# Thermostat_Master.net
KiCad netlist of a schematic drawn in Altium Designer
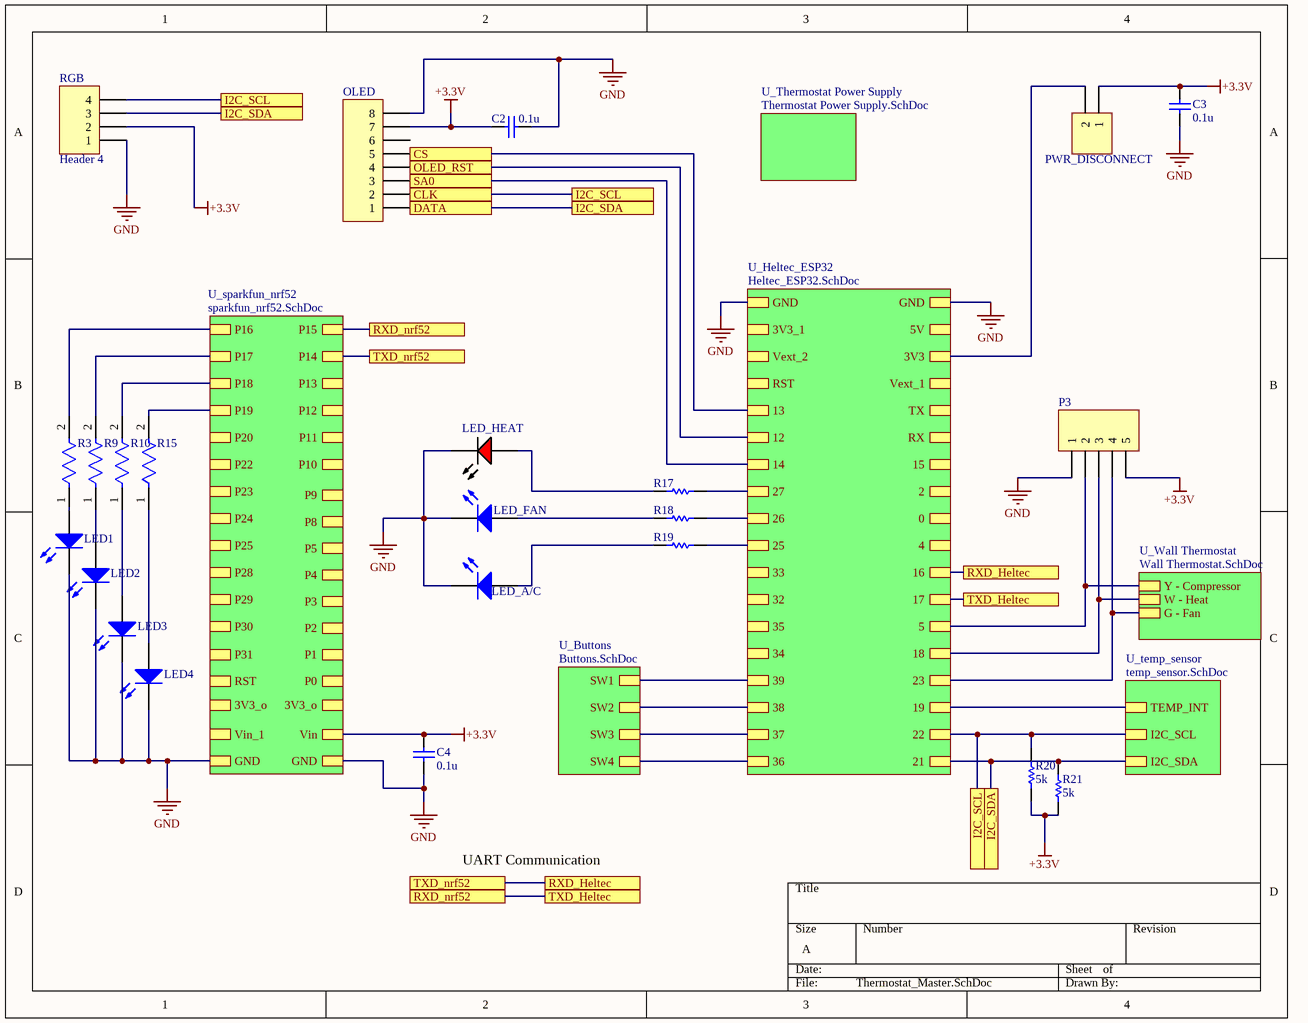
[diagram p0: Thermostat_Master.SchDoc]

(export (version "E")
  (design (tool "Eeschema 10.0.6"))
  (components
    (comp (ref "C2")
      (value "0.1u")
      (footprint "CAPC2013X145X50LL20T25")
      (description "C0805C104Z5VACTU")
      (fields (field (name "MANUFACTURER") "Kemet"))
      (libsource (lib "Altium Content Vault") (part "CAP"))
    )
    (comp (ref "C3")
      (value "0.1u")
      (footprint "CAPC2013X145X50LL20T25")
      (description "C0805C104Z5VACTU")
      (fields (field (name "MANUFACTURER") "Kemet"))
      (libsource (lib "Altium Content Vault") (part "CAP"))
    )
    (comp (ref "C4")
      (value "0.1u")
      (footprint "CAPC2013X145X50LL20T25")
      (description "C0805C104Z5VACTU")
      (fields (field (name "MANUFACTURER") "Kemet"))
      (libsource (lib "Altium Content Vault") (part "CAP"))
    )
    (comp (ref "LED1")
      (value "~")
      (footprint "1206_A")
      (description "QTLP650C4TR\r\n1206 green led")
      (fields (field (name "PARTNUMBER") "150120VS75000") (field (name "MANUFACTURER") "Wuerth Elektronik"))
      (libsource (lib "Altium Content Vault") (part "WE-LED_K1A2-2"))
    )
    (comp (ref "LED2")
      (value "~")
      (footprint "1206_A")
      (description "QTLP650C4TR\r\n1206 green led")
      (fields (field (name "PARTNUMBER") "150120VS75000") (field (name "MANUFACTURER") "Wuerth Elektronik"))
      (libsource (lib "Altium Content Vault") (part "WE-LED_K1A2-2"))
    )
    (comp (ref "LED3")
      (value "~")
      (footprint "1206_A")
      (description "QTLP650C4TR\r\n1206 green led")
      (fields (field (name "PARTNUMBER") "150120VS75000") (field (name "MANUFACTURER") "Wuerth Elektronik"))
      (libsource (lib "Altium Content Vault") (part "WE-LED_K1A2-2"))
    )
    (comp (ref "LED4")
      (value "~")
      (footprint "1206_A")
      (description "QTLP650C4TR\r\n1206 green led")
      (fields (field (name "PARTNUMBER") "150120VS75000") (field (name "MANUFACTURER") "Wuerth Elektronik"))
      (libsource (lib "Altium Content Vault") (part "WE-LED_K1A2-2"))
    )
    (comp (ref "LED_A/C")
      (value "~")
      (footprint "1206_A")
      (description "QTLP650C4TR\r\n1206 green led")
      (fields (field (name "PARTNUMBER") "LTST-C150TBKT"))
      (libsource (lib "Altium Content Vault") (part "WE-LED_K1A2-2"))
    )
    (comp (ref "LED_FAN")
      (value "~")
      (footprint "1206_A")
      (description "LTST-C150GKT\r\n1206 green led")
      (fields (field (name "PARTNUMBER") "LTST-C150GKT"))
      (libsource (lib "Altium Content Vault") (part "WE-LED_K1A2-2"))
    )
    (comp (ref "LED_HEAT")
      (value "LTST-C150KRKT")
      (footprint "LTST-C150KRKT_V")
      (description "LED Red, 62.5 mW, 50 mA, -30 to 85 degC, 2-Pin SMD, RoHS, Tape and Reel")
      (fields (field (name "MANUFACTURER") "Lite-On"))
      (libsource (lib "Altium Content Vault") (part "LED-RED-AK-2"))
    )
    (comp (ref "OLED")
      (value "Header 8")
      (footprint "HDR1X8")
      (description "Header, 8-Pin")
      (fields (field (name "PUBLISHER") "Altium Limited"))
      (libsource (lib "Miscellaneous Connectors") (part "Header 8"))
    )
    (comp (ref "P3")
      (value "Header 5")
      (footprint "HDR1X5")
      (description "Header, 5-Pin")
      (fields (field (name "PUBLISHER") "Altium Limited"))
      (libsource (lib "Miscellaneous Connectors") (part "Header 5"))
    )
    (comp (ref "PWR_DISCONNECT")
      (value "Header 2")
      (footprint "HDR1X2")
      (description "Header, 2-Pin")
      (fields (field (name "PUBLISHER") "Altium Limited"))
      (libsource (lib "Miscellaneous Connectors") (part "Header 2"))
    )
    (comp (ref "R3")
      (value "~")
      (footprint "FP-RC1206-MFG")
      (description "360 ohms resistor \r\n1206 package")
      (fields
        (field (name "MANUFACTURER PART NUMBER") "RC1206JR-070RL")
        (field (name "MANUFACTURER") "YAGEO")
      )
      (libsource (lib "Altium Content Vault") (part "1029c3af85768c4190bb7ad29bc67b5"))
    )
    (comp (ref "R9")
      (value "~")
      (footprint "FP-RC1206-MFG")
      (description "360 ohms resistor \r\n1206 package")
      (fields
        (field (name "MANUFACTURER PART NUMBER") "RC1206JR-070RL")
        (field (name "MANUFACTURER") "YAGEO")
      )
      (libsource (lib "Altium Content Vault") (part "1029c3af85768c4190bb7ad29bc67b5"))
    )
    (comp (ref "R10")
      (value "~")
      (footprint "FP-RC1206-MFG")
      (description "360 ohms resistor \r\n1206 package")
      (fields
        (field (name "MANUFACTURER PART NUMBER") "RC1206JR-070RL")
        (field (name "MANUFACTURER") "YAGEO")
      )
      (libsource (lib "Altium Content Vault") (part "1029c3af85768c4190bb7ad29bc67b5"))
    )
    (comp (ref "R15")
      (value "~")
      (footprint "FP-RC1206-MFG")
      (description "360 ohms resistor \r\n1206 package")
      (fields
        (field (name "MANUFACTURER PART NUMBER") "RC1206JR-070RL")
        (field (name "MANUFACTURER") "YAGEO")
      )
      (libsource (lib "Altium Content Vault") (part "1029c3af85768c4190bb7ad29bc67b5"))
    )
    (comp (ref "R17")
      (value "RC0805FR-07100RL")
      (footprint "RESC2013X60X35ML10T20")
      (description "Chip Resistor, 100 Ohm, +/-1%, 0.125 W, -55 to 155 degC, 0805 (2012 Metric), RoHS, Tape and Reel")
      (fields (field (name "TOLERANCE") "1%") (field (name "MANUFACTURER") "Yageo"))
      (libsource (lib "Altium Content Vault") (part "RES-2"))
    )
    (comp (ref "R18")
      (value "RC0805FR-07100RL")
      (footprint "RESC2013X60X35ML10T20")
      (description "Chip Resistor, 100 Ohm, +/-1%, 0.125 W, -55 to 155 degC, 0805 (2012 Metric), RoHS, Tape and Reel")
      (fields (field (name "TOLERANCE") "1%") (field (name "MANUFACTURER") "Yageo"))
      (libsource (lib "Altium Content Vault") (part "RES-2"))
    )
    (comp (ref "R19")
      (value "RC0805FR-07100RL")
      (footprint "RESC2013X60X35ML10T20")
      (description "Chip Resistor, 100 Ohm, +/-1%, 0.125 W, -55 to 155 degC, 0805 (2012 Metric), RoHS, Tape and Reel")
      (fields (field (name "TOLERANCE") "1%") (field (name "MANUFACTURER") "Yageo"))
      (libsource (lib "Altium Content Vault") (part "RES-2"))
    )
    (comp (ref "R20")
      (value "5k")
      (footprint "RESC2013X70X40LL20T20")
      (description "2012")
      (fields (field (name "PART NUMBER") "ERJ-6GEYJ471V") (field (name "MANUFACTURER") "Panasonic"))
      (libsource (lib "Altium Content Vault") (part "RES"))
    )
    (comp (ref "R21")
      (value "5k")
      (footprint "RESC2013X70X40LL20T20")
      (description "2012")
      (fields (field (name "PART NUMBER") "ERJ-6GEYJ471V") (field (name "MANUFACTURER") "Panasonic"))
      (libsource (lib "Altium Content Vault") (part "RES"))
    )
    (comp (ref "RGB")
      (value "Header 4")
      (footprint "HDR1X4")
      (description "Header, 4-Pin")
      (fields (field (name "PUBLISHER") "Altium Limited"))
      (libsource (lib "Miscellaneous Connectors") (part "Header 4"))
    )
  )
  (nets
    (net (code "1") (name "+3.3V") (class "Default")
      (node (ref "C2") (pin "2") (pinfunction "2_2") (pintype "passive"))
      (node (ref "C3") (pin "2") (pinfunction "2_2") (pintype "passive"))
      (node (ref "C4") (pin "2") (pinfunction "2_2") (pintype "passive"))
      (node (ref "OLED") (pin "7") (pinfunction "7_7") (pintype "passive"))
      (node (ref "P3") (pin "5") (pinfunction "5_5") (pintype "passive"))
      (node (ref "PWR_DISCONNECT") (pin "1") (pinfunction "1_1") (pintype "passive"))
      (node (ref "R20") (pin "1") (pinfunction "1_1") (pintype "passive"))
      (node (ref "R21") (pin "1") (pinfunction "1_1") (pintype "passive"))
      (node (ref "RGB") (pin "2") (pinfunction "2_2") (pintype "passive"))
    )
    (net (code "4") (name "/3V3") (class "Default")
      (node (ref "PWR_DISCONNECT") (pin "2") (pinfunction "2_2") (pintype "passive"))
    )
    (net (code "9") (name "/5") (class "Default")
      (node (ref "P3") (pin "2") (pinfunction "2_2") (pintype "passive"))
    )
    (net (code "12") (name "/18") (class "Default")
      (node (ref "P3") (pin "3") (pinfunction "3_3") (pintype "passive"))
    )
    (net (code "14") (name "/23") (class "Default")
      (node (ref "P3") (pin "4") (pinfunction "4_4") (pintype "passive"))
    )
    (net (code "15") (name "/25") (class "Default")
      (node (ref "R19") (pin "2") (pinfunction "2_2") (pintype "passive"))
    )
    (net (code "16") (name "/26") (class "Default")
      (node (ref "R18") (pin "2") (pinfunction "2_2") (pintype "passive"))
    )
    (net (code "17") (name "/27") (class "Default")
      (node (ref "R17") (pin "2") (pinfunction "2_2") (pintype "passive"))
    )
    (net (code "26") (name "/CLK") (class "Default")
      (node (ref "OLED") (pin "2") (pinfunction "2_2") (pintype "passive"))
      (node (ref "R20") (pin "2") (pinfunction "2_2") (pintype "passive"))
      (node (ref "RGB") (pin "4") (pinfunction "4_4") (pintype "passive"))
    )
    (net (code "27") (name "/CS") (class "Default")
      (node (ref "OLED") (pin "5") (pinfunction "5_5") (pintype "passive"))
    )
    (net (code "28") (name "/DATA") (class "Default")
      (node (ref "OLED") (pin "1") (pinfunction "1_1") (pintype "passive"))
      (node (ref "R21") (pin "2") (pinfunction "2_2") (pintype "passive"))
      (node (ref "RGB") (pin "3") (pinfunction "3_3") (pintype "passive"))
    )
    (net (code "29") (name "/OLED_RST") (class "Default")
      (node (ref "OLED") (pin "4") (pinfunction "4_4") (pintype "passive"))
    )
    (net (code "42") (name "/P16") (class "Default")
      (node (ref "R3") (pin "2") (pinfunction "2_2") (pintype "passive"))
    )
    (net (code "43") (name "/P17") (class "Default")
      (node (ref "R9") (pin "2") (pinfunction "2_2") (pintype "passive"))
    )
    (net (code "44") (name "/P18") (class "Default")
      (node (ref "R10") (pin "2") (pinfunction "2_2") (pintype "passive"))
    )
    (net (code "45") (name "/P19") (class "Default")
      (node (ref "R15") (pin "2") (pinfunction "2_2") (pintype "passive"))
    )
    (net (code "60") (name "/SA0") (class "Default")
      (node (ref "OLED") (pin "3") (pinfunction "3_3") (pintype "passive"))
    )
    (net (code "65") (name "GND") (class "Default")
      (node (ref "C2") (pin "1") (pinfunction "1_1") (pintype "passive"))
      (node (ref "C3") (pin "1") (pinfunction "1_1") (pintype "passive"))
      (node (ref "C4") (pin "1") (pinfunction "1_1") (pintype "passive"))
      (node (ref "LED1") (pin "1") (pinfunction "K_1") (pintype "passive"))
      (node (ref "LED2") (pin "1") (pinfunction "K_1") (pintype "passive"))
      (node (ref "LED3") (pin "1") (pinfunction "K_1") (pintype "passive"))
      (node (ref "LED4") (pin "1") (pinfunction "K_1") (pintype "passive"))
      (node (ref "LED_A/C") (pin "1") (pinfunction "K_1") (pintype "passive"))
      (node (ref "LED_FAN") (pin "1") (pinfunction "K_1") (pintype "passive"))
      (node (ref "LED_HEAT") (pin "2") (pinfunction "K_2") (pintype "passive"))
      (node (ref "OLED") (pin "8") (pinfunction "8_8") (pintype "passive"))
      (node (ref "P3") (pin "1") (pinfunction "1_1") (pintype "passive"))
      (node (ref "RGB") (pin "1") (pinfunction "1_1") (pintype "passive"))
    )
    (net (code "66") (name "Net-(LED1-A)") (class "Default")
      (node (ref "LED1") (pin "2") (pinfunction "A_2") (pintype "passive"))
      (node (ref "R3") (pin "1") (pinfunction "1_1") (pintype "passive"))
    )
    (net (code "67") (name "Net-(LED2-A)") (class "Default")
      (node (ref "LED2") (pin "2") (pinfunction "A_2") (pintype "passive"))
      (node (ref "R9") (pin "1") (pinfunction "1_1") (pintype "passive"))
    )
    (net (code "68") (name "Net-(LED3-A)") (class "Default")
      (node (ref "LED3") (pin "2") (pinfunction "A_2") (pintype "passive"))
      (node (ref "R10") (pin "1") (pinfunction "1_1") (pintype "passive"))
    )
    (net (code "69") (name "Net-(LED4-A)") (class "Default")
      (node (ref "LED4") (pin "2") (pinfunction "A_2") (pintype "passive"))
      (node (ref "R15") (pin "1") (pinfunction "1_1") (pintype "passive"))
    )
    (net (code "70") (name "Net-(LED_A/C-A)") (class "Default")
      (node (ref "LED_A/C") (pin "2") (pinfunction "A_2") (pintype "passive"))
      (node (ref "R19") (pin "1") (pinfunction "1_1") (pintype "passive"))
    )
    (net (code "71") (name "Net-(LED_FAN-A)") (class "Default")
      (node (ref "LED_FAN") (pin "2") (pinfunction "A_2") (pintype "passive"))
      (node (ref "R18") (pin "1") (pinfunction "1_1") (pintype "passive"))
    )
    (net (code "72") (name "Net-(LED_HEAT-A)") (class "Default")
      (node (ref "LED_HEAT") (pin "1") (pinfunction "A_1") (pintype "passive"))
      (node (ref "R17") (pin "1") (pinfunction "1_1") (pintype "passive"))
    )
    (net (code "73") (name "unconnected-(OLED-Pad6)") (class "Default")
      (node (ref "OLED") (pin "6") (pinfunction "6_6") (pintype "passive"))
    )
  )
)
